# design.net
KiCad netlist of a schematic drawn in Altium Designer
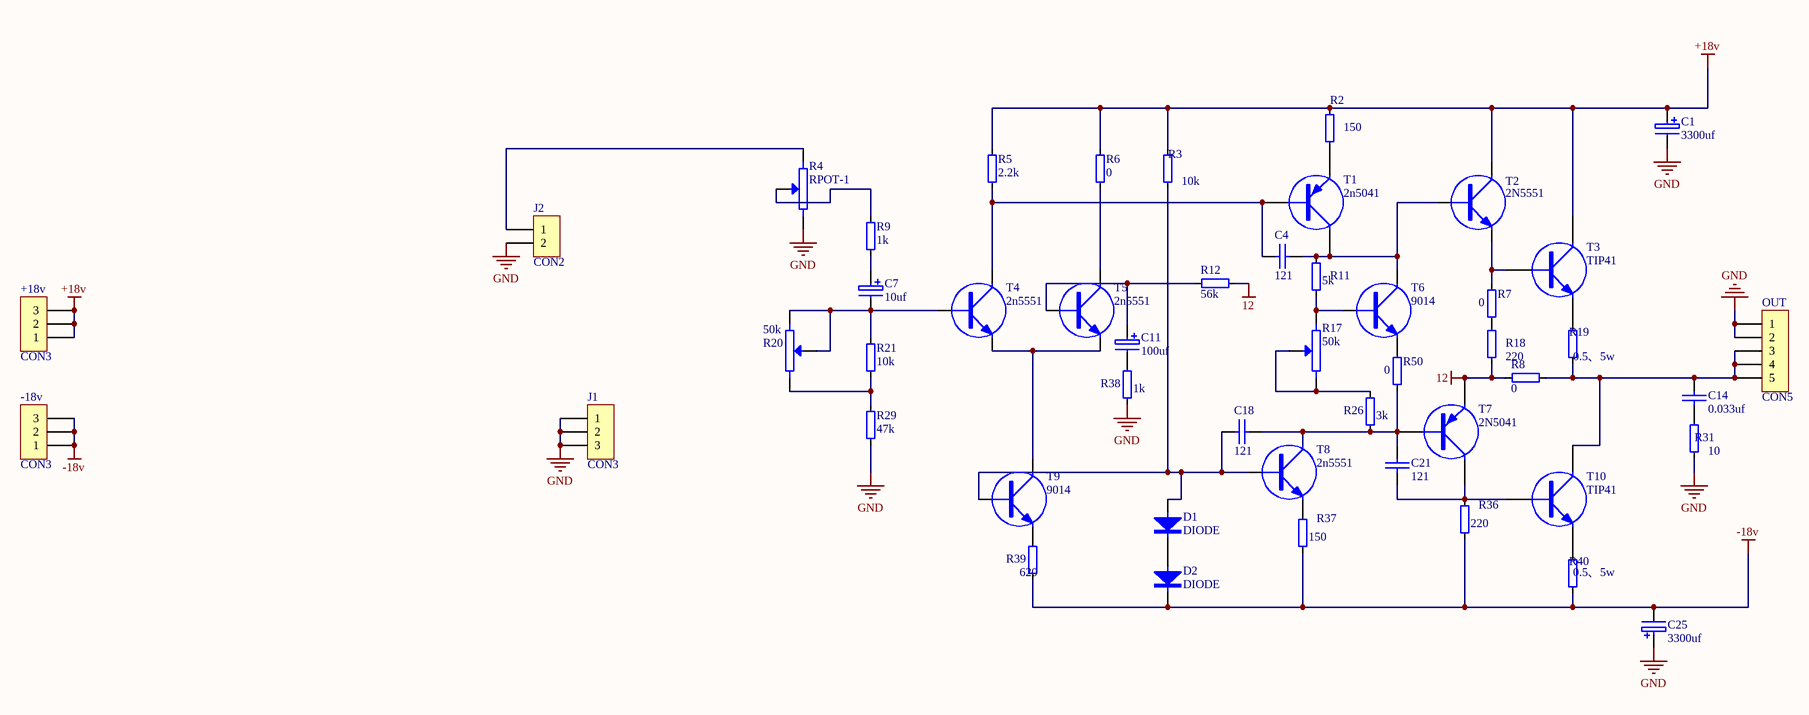
[diagram p0: 前级.SchDoc]

(export (version "E")
  (design (tool "Eeschema 10.0.6"))
  (components
    (comp (ref "+18v")
      (value "CON3")
      (footprint "SIP-3")
      (description "Connector")
      (libsource (lib "Plugs插头") (part "CON3"))
    )
    (comp (ref "-18v")
      (value "CON3")
      (footprint "SIP-3")
      (description "Connector")
      (libsource (lib "Plugs插头") (part "CON3"))
    )
    (comp (ref "C1") (value "3300uf") (footprint "C14") (libsource (lib "C电容") (part "CAP3")))
    (comp (ref "C4") (value "121") (footprint "RAD0.1") (libsource (lib "常用元件库") (part "CAP")))
    (comp (ref "C7") (value "10uf") (footprint "CAO1") (libsource (lib "C电容") (part "CAP3")))
    (comp (ref "C11") (value "100uf") (footprint "CAO1") (libsource (lib "C电容") (part "CAP3")))
    (comp (ref "C14") (value "0.033uf") (footprint "RAD0.1") (libsource (lib "常用元件库") (part "CAP")))
    (comp (ref "C18") (value "121") (footprint "RAD0.1") (libsource (lib "常用元件库") (part "CAP")))
    (comp (ref "C21") (value "121") (footprint "RAD0.1") (libsource (lib "常用元件库") (part "CAP")))
    (comp (ref "C25") (value "3300uf") (footprint "C14") (libsource (lib "C电容") (part "CAP3")))
    (comp (ref "D1") (value "DIODE") (footprint "DIODE0.4") (libsource (lib "Diode二极管") (part "DIODE")))
    (comp (ref "D2") (value "DIODE") (footprint "DIODE0.4") (libsource (lib "Diode二极管") (part "DIODE")))
    (comp (ref "J1")
      (value "CON3")
      (footprint "SIP-3")
      (description "Connector")
      (libsource (lib "") (part "CON3_1"))
    )
    (comp (ref "J2")
      (value "CON2")
      (footprint "sip-2")
      (description "Connector")
      (libsource (lib "接口") (part "CON2"))
    )
    (comp (ref "OUT")
      (value "CON5")
      (footprint "SIP-5")
      (description "Connector")
      (libsource (lib "Plugs插头") (part "CON5"))
    )
    (comp (ref "R2") (value "150") (footprint "AXIAL0.4") (libsource (lib "电阻") (part "RES")))
    (comp (ref "R3") (value "10k") (footprint "AXIAL0.4") (libsource (lib "电阻") (part "RES")))
    (comp (ref "R4")
      (value "RPOT-1")
      (footprint "RVR-A")
      (description "Potentiometer")
      (libsource (lib "R电阻") (part "RPOT-1"))
    )
    (comp (ref "R5") (value "2.2k") (footprint "AXIAL0.4") (libsource (lib "电阻") (part "RES")))
    (comp (ref "R6") (value "0") (footprint "AXIAL0.4") (libsource (lib "电阻") (part "RES")))
    (comp (ref "R7") (value "0") (footprint "AXIAL0.4") (libsource (lib "电阻") (part "RES")))
    (comp (ref "R8") (value "0") (footprint "AXIAL0.4") (libsource (lib "电阻") (part "RES")))
    (comp (ref "R9") (value "1k") (footprint "AXIAL0.4") (libsource (lib "电阻") (part "RES")))
    (comp (ref "R11") (value "5k") (footprint "AXIAL0.4") (libsource (lib "电阻") (part "RES")))
    (comp (ref "R12") (value "56k") (footprint "AXIAL0.4") (libsource (lib "电阻") (part "RES")))
    (comp (ref "R17")
      (value "50k")
      (footprint "RVR-A")
      (description "Potentiometer")
      (libsource (lib "R电阻") (part "RPOT-1"))
    )
    (comp (ref "R18") (value "220") (footprint "AXIAL0.4") (libsource (lib "电阻") (part "RES")))
    (comp (ref "R19") (value "0.5、5w") (footprint "AXIAL0.4") (libsource (lib "电阻") (part "RES")))
    (comp (ref "R20")
      (value "50k")
      (footprint "RVR-A")
      (description "Potentiometer")
      (libsource (lib "R电阻") (part "RPOT-1"))
    )
    (comp (ref "R21") (value "10k") (footprint "AXIAL0.4") (libsource (lib "电阻") (part "RES")))
    (comp (ref "R26") (value "3k") (footprint "AXIAL0.4") (libsource (lib "电阻") (part "RES")))
    (comp (ref "R29") (value "47k") (footprint "AXIAL0.4") (libsource (lib "电阻") (part "RES")))
    (comp (ref "R31") (value "10") (footprint "AXIAL0.4") (libsource (lib "电阻") (part "RES")))
    (comp (ref "R36") (value "220") (footprint "AXIAL0.4") (libsource (lib "电阻") (part "RES")))
    (comp (ref "R37") (value "150") (footprint "AXIAL0.4") (libsource (lib "电阻") (part "RES")))
    (comp (ref "R38") (value "1k") (footprint "AXIAL0.4") (libsource (lib "电阻") (part "RES")))
    (comp (ref "R39") (value "620") (footprint "AXIAL0.4") (libsource (lib "电阻") (part "RES")))
    (comp (ref "R40") (value "0.5、5w") (footprint "AXIAL0.4") (libsource (lib "电阻") (part "RES")))
    (comp (ref "R50") (value "0") (footprint "AXIAL0.4") (libsource (lib "电阻") (part "RES")))
    (comp (ref "T1") (value "2n5041") (footprint "TO92B") (libsource (lib "V三极管") (part "9012")))
    (comp (ref "T2") (value "2N5551") (footprint "TO92B") (libsource (lib "V三极管") (part "9014")))
    (comp (ref "T3")
      (value "TIP41")
      (footprint "TO-220")
      (description "NPN PLASTIC POWER TRANSISTORS")
      (libsource (lib "V三极管") (part "TIP41"))
    )
    (comp (ref "T4") (value "2n5551") (footprint "TO92B") (libsource (lib "V三极管") (part "9014")))
    (comp (ref "T5") (value "2n5551") (footprint "TO92B") (libsource (lib "V三极管") (part "9014")))
    (comp (ref "T6") (value "9014") (footprint "TO92B") (libsource (lib "V三极管") (part "9014")))
    (comp (ref "T7") (value "2N5041") (footprint "TO92B") (libsource (lib "V三极管") (part "9012")))
    (comp (ref "T8") (value "2n5551") (footprint "TO92B") (libsource (lib "V三极管") (part "9014")))
    (comp (ref "T9") (value "9014") (footprint "TO92B") (libsource (lib "V三极管") (part "9014")))
    (comp (ref "T10")
      (value "TIP41")
      (footprint "TO-220")
      (description "NPN PLASTIC POWER TRANSISTORS")
      (libsource (lib "V三极管") (part "TIP41"))
    )
  )
  (nets
    (net (code "1") (name "+18v") (class "Default")
      (node (ref "+18v") (pin "1") (pinfunction "1_1") (pintype "passive"))
      (node (ref "+18v") (pin "2") (pinfunction "2_2") (pintype "passive"))
      (node (ref "+18v") (pin "3") (pinfunction "3_3") (pintype "passive"))
      (node (ref "C1") (pin "1") (pintype "passive"))
      (node (ref "R2") (pin "1") (pinfunction "1_1") (pintype "passive"))
      (node (ref "R3") (pin "1") (pinfunction "1_1") (pintype "passive"))
      (node (ref "R5") (pin "1") (pinfunction "1_1") (pintype "passive"))
      (node (ref "R6") (pin "1") (pinfunction "1_1") (pintype "passive"))
      (node (ref "T2") (pin "3") (pinfunction "C_3") (pintype "passive"))
      (node (ref "T3") (pin "2") (pinfunction "C_2") (pintype "passive"))
    )
    (net (code "2") (name "-18v") (class "Default")
      (node (ref "-18v") (pin "1") (pinfunction "1_1") (pintype "passive"))
      (node (ref "-18v") (pin "2") (pinfunction "2_2") (pintype "passive"))
      (node (ref "-18v") (pin "3") (pinfunction "3_3") (pintype "passive"))
      (node (ref "C25") (pin "2") (pintype "passive"))
      (node (ref "D2") (pin "2") (pinfunction "2_2") (pintype "passive"))
      (node (ref "R36") (pin "2") (pinfunction "2_2") (pintype "passive"))
      (node (ref "R37") (pin "2") (pinfunction "2_2") (pintype "passive"))
      (node (ref "R39") (pin "2") (pinfunction "2_2") (pintype "passive"))
      (node (ref "R40") (pin "2") (pinfunction "2_2") (pintype "passive"))
    )
    (net (code "3") (name "12") (class "Default")
      (node (ref "R12") (pin "2") (pinfunction "2_2") (pintype "passive"))
      (node (ref "R18") (pin "2") (pinfunction "2_2") (pintype "passive"))
      (node (ref "R8") (pin "1") (pinfunction "1_1") (pintype "passive"))
      (node (ref "T7") (pin "1") (pinfunction "E_1") (pintype "passive"))
    )
    (net (code "4") (name "GND") (class "Default")
      (node (ref "C1") (pin "2") (pintype "passive"))
      (node (ref "C25") (pin "1") (pintype "passive"))
      (node (ref "J1") (pin "1") (pinfunction "1_1") (pintype "passive"))
      (node (ref "J1") (pin "2") (pinfunction "2_2") (pintype "passive"))
      (node (ref "J1") (pin "3") (pinfunction "3_3") (pintype "passive"))
      (node (ref "J2") (pin "2") (pinfunction "2_2") (pintype "passive"))
      (node (ref "OUT") (pin "1") (pinfunction "1_1") (pintype "passive"))
      (node (ref "OUT") (pin "2") (pinfunction "2_2") (pintype "passive"))
      (node (ref "R29") (pin "2") (pinfunction "2_2") (pintype "passive"))
      (node (ref "R31") (pin "2") (pinfunction "2_2") (pintype "passive"))
      (node (ref "R38") (pin "2") (pinfunction "2_2") (pintype "passive"))
      (node (ref "R4") (pin "1") (pinfunction "1_1") (pintype "passive"))
    )
    (net (code "5") (name "Net-(C7-Pad1)") (class "Default")
      (node (ref "C7") (pin "1") (pintype "passive"))
      (node (ref "R9") (pin "2") (pinfunction "2_2") (pintype "passive"))
    )
    (net (code "6") (name "Net-(C11-Pad2)") (class "Default")
      (node (ref "C11") (pin "2") (pintype "passive"))
      (node (ref "R38") (pin "1") (pinfunction "1_1") (pintype "passive"))
    )
    (net (code "7") (name "Net-(C14-Pad1)") (class "Default")
      (node (ref "C14") (pin "1") (pinfunction "1_1") (pintype "passive"))
      (node (ref "R31") (pin "1") (pinfunction "1_1") (pintype "passive"))
    )
    (net (code "8") (name "Net-(D1-Pad2)") (class "Default")
      (node (ref "D1") (pin "2") (pinfunction "2_2") (pintype "passive"))
      (node (ref "D2") (pin "1") (pinfunction "1_1") (pintype "passive"))
    )
    (net (code "9") (name "Net-(J2-Pad1)") (class "Default")
      (node (ref "J2") (pin "1") (pinfunction "1_1") (pintype "passive"))
      (node (ref "R4") (pin "3") (pinfunction "3_3") (pintype "passive"))
    )
    (net (code "10") (name "Net-(R4-W)") (class "Default")
      (node (ref "R4") (pin "2") (pinfunction "W_2") (pintype "passive"))
      (node (ref "R9") (pin "1") (pinfunction "1_1") (pintype "passive"))
    )
    (net (code "11") (name "Net-(R17-W)") (class "Default")
      (node (ref "R17") (pin "1") (pinfunction "1_1") (pintype "passive"))
      (node (ref "R17") (pin "2") (pinfunction "W_2") (pintype "passive"))
      (node (ref "R26") (pin "1") (pinfunction "1_1") (pintype "passive"))
    )
    (net (code "12") (name "Net-(R18-Pad1)") (class "Default")
      (node (ref "R18") (pin "1") (pinfunction "1_1") (pintype "passive"))
      (node (ref "R7") (pin "2") (pinfunction "2_2") (pintype "passive"))
    )
    (net (code "13") (name "Net-(R20-Pad3)") (class "Default")
      (node (ref "R20") (pin "3") (pinfunction "3_3") (pintype "passive"))
      (node (ref "R21") (pin "2") (pinfunction "2_2") (pintype "passive"))
      (node (ref "R29") (pin "1") (pinfunction "1_1") (pintype "passive"))
    )
    (net (code "14") (name "Net-(R20-W)") (class "Default")
      (node (ref "C7") (pin "2") (pintype "passive"))
      (node (ref "R20") (pin "1") (pinfunction "1_1") (pintype "passive"))
      (node (ref "R20") (pin "2") (pinfunction "W_2") (pintype "passive"))
      (node (ref "R21") (pin "1") (pinfunction "1_1") (pintype "passive"))
      (node (ref "T4") (pin "2") (pinfunction "B_2") (pintype "passive"))
    )
    (net (code "15") (name "Net-(T1-B)") (class "Default")
      (node (ref "C4") (pin "1") (pinfunction "1_1") (pintype "passive"))
      (node (ref "R5") (pin "2") (pinfunction "2_2") (pintype "passive"))
      (node (ref "T1") (pin "2") (pinfunction "B_2") (pintype "passive"))
      (node (ref "T4") (pin "3") (pinfunction "C_3") (pintype "passive"))
    )
    (net (code "16") (name "Net-(T1-C)") (class "Default")
      (node (ref "C4") (pin "2") (pinfunction "2_2") (pintype "passive"))
      (node (ref "R11") (pin "1") (pinfunction "1_1") (pintype "passive"))
      (node (ref "T1") (pin "3") (pinfunction "C_3") (pintype "passive"))
      (node (ref "T2") (pin "2") (pinfunction "B_2") (pintype "passive"))
      (node (ref "T6") (pin "3") (pinfunction "C_3") (pintype "passive"))
    )
    (net (code "17") (name "Net-(T1-E)") (class "Default")
      (node (ref "R2") (pin "2") (pinfunction "2_2") (pintype "passive"))
      (node (ref "T1") (pin "1") (pinfunction "E_1") (pintype "passive"))
    )
    (net (code "18") (name "Net-(T2-E)") (class "Default")
      (node (ref "R7") (pin "1") (pinfunction "1_1") (pintype "passive"))
      (node (ref "T2") (pin "1") (pinfunction "E_1") (pintype "passive"))
      (node (ref "T3") (pin "1") (pinfunction "B_1") (pintype "passive"))
    )
    (net (code "19") (name "Net-(T3-E)") (class "Default")
      (node (ref "R19") (pin "1") (pinfunction "1_1") (pintype "passive"))
      (node (ref "T3") (pin "3") (pinfunction "E_3") (pintype "passive"))
    )
    (net (code "20") (name "Net-(T4-E)") (class "Default")
      (node (ref "T4") (pin "1") (pinfunction "E_1") (pintype "passive"))
      (node (ref "T5") (pin "1") (pinfunction "E_1") (pintype "passive"))
      (node (ref "T9") (pin "3") (pinfunction "C_3") (pintype "passive"))
    )
    (net (code "21") (name "Net-(T5-B)") (class "Default")
      (node (ref "C11") (pin "1") (pintype "passive"))
      (node (ref "R12") (pin "1") (pinfunction "1_1") (pintype "passive"))
      (node (ref "T5") (pin "2") (pinfunction "B_2") (pintype "passive"))
    )
    (net (code "22") (name "Net-(T5-C)") (class "Default")
      (node (ref "R6") (pin "2") (pinfunction "2_2") (pintype "passive"))
      (node (ref "T5") (pin "3") (pinfunction "C_3") (pintype "passive"))
    )
    (net (code "23") (name "Net-(T6-B)") (class "Default")
      (node (ref "R11") (pin "2") (pinfunction "2_2") (pintype "passive"))
      (node (ref "R17") (pin "3") (pinfunction "3_3") (pintype "passive"))
      (node (ref "T6") (pin "2") (pinfunction "B_2") (pintype "passive"))
    )
    (net (code "24") (name "Net-(T6-E)") (class "Default")
      (node (ref "R50") (pin "1") (pinfunction "1_1") (pintype "passive"))
      (node (ref "T6") (pin "1") (pinfunction "E_1") (pintype "passive"))
    )
    (net (code "25") (name "Net-(T7-B)") (class "Default")
      (node (ref "C18") (pin "2") (pinfunction "2_2") (pintype "passive"))
      (node (ref "C21") (pin "2") (pinfunction "2_2") (pintype "passive"))
      (node (ref "R26") (pin "2") (pinfunction "2_2") (pintype "passive"))
      (node (ref "R50") (pin "2") (pinfunction "2_2") (pintype "passive"))
      (node (ref "T7") (pin "2") (pinfunction "B_2") (pintype "passive"))
      (node (ref "T8") (pin "3") (pinfunction "C_3") (pintype "passive"))
    )
    (net (code "26") (name "Net-(T8-B)") (class "Default")
      (node (ref "C18") (pin "1") (pinfunction "1_1") (pintype "passive"))
      (node (ref "D1") (pin "1") (pinfunction "1_1") (pintype "passive"))
      (node (ref "R3") (pin "2") (pinfunction "2_2") (pintype "passive"))
      (node (ref "T8") (pin "2") (pinfunction "B_2") (pintype "passive"))
      (node (ref "T9") (pin "2") (pinfunction "B_2") (pintype "passive"))
    )
    (net (code "27") (name "Net-(T8-E)") (class "Default")
      (node (ref "R37") (pin "1") (pinfunction "1_1") (pintype "passive"))
      (node (ref "T8") (pin "1") (pinfunction "E_1") (pintype "passive"))
    )
    (net (code "28") (name "Net-(T9-E)") (class "Default")
      (node (ref "R39") (pin "1") (pinfunction "1_1") (pintype "passive"))
      (node (ref "T9") (pin "1") (pinfunction "E_1") (pintype "passive"))
    )
    (net (code "29") (name "Net-(T10-B)") (class "Default")
      (node (ref "C21") (pin "1") (pinfunction "1_1") (pintype "passive"))
      (node (ref "R36") (pin "1") (pinfunction "1_1") (pintype "passive"))
      (node (ref "T10") (pin "1") (pinfunction "B_1") (pintype "passive"))
      (node (ref "T7") (pin "3") (pinfunction "C_3") (pintype "passive"))
    )
    (net (code "30") (name "Net-(T10-C)") (class "Default")
      (node (ref "C14") (pin "2") (pinfunction "2_2") (pintype "passive"))
      (node (ref "OUT") (pin "3") (pinfunction "3_3") (pintype "passive"))
      (node (ref "OUT") (pin "4") (pinfunction "4_4") (pintype "passive"))
      (node (ref "OUT") (pin "5") (pinfunction "5_5") (pintype "passive"))
      (node (ref "R19") (pin "2") (pinfunction "2_2") (pintype "passive"))
      (node (ref "R8") (pin "2") (pinfunction "2_2") (pintype "passive"))
      (node (ref "T10") (pin "2") (pinfunction "C_2") (pintype "passive"))
    )
    (net (code "31") (name "Net-(T10-E)") (class "Default")
      (node (ref "R40") (pin "1") (pinfunction "1_1") (pintype "passive"))
      (node (ref "T10") (pin "3") (pinfunction "E_3") (pintype "passive"))
    )
  )
)
